# flip_lamp.net
KiCad netlist of a schematic drawn in EAGLE
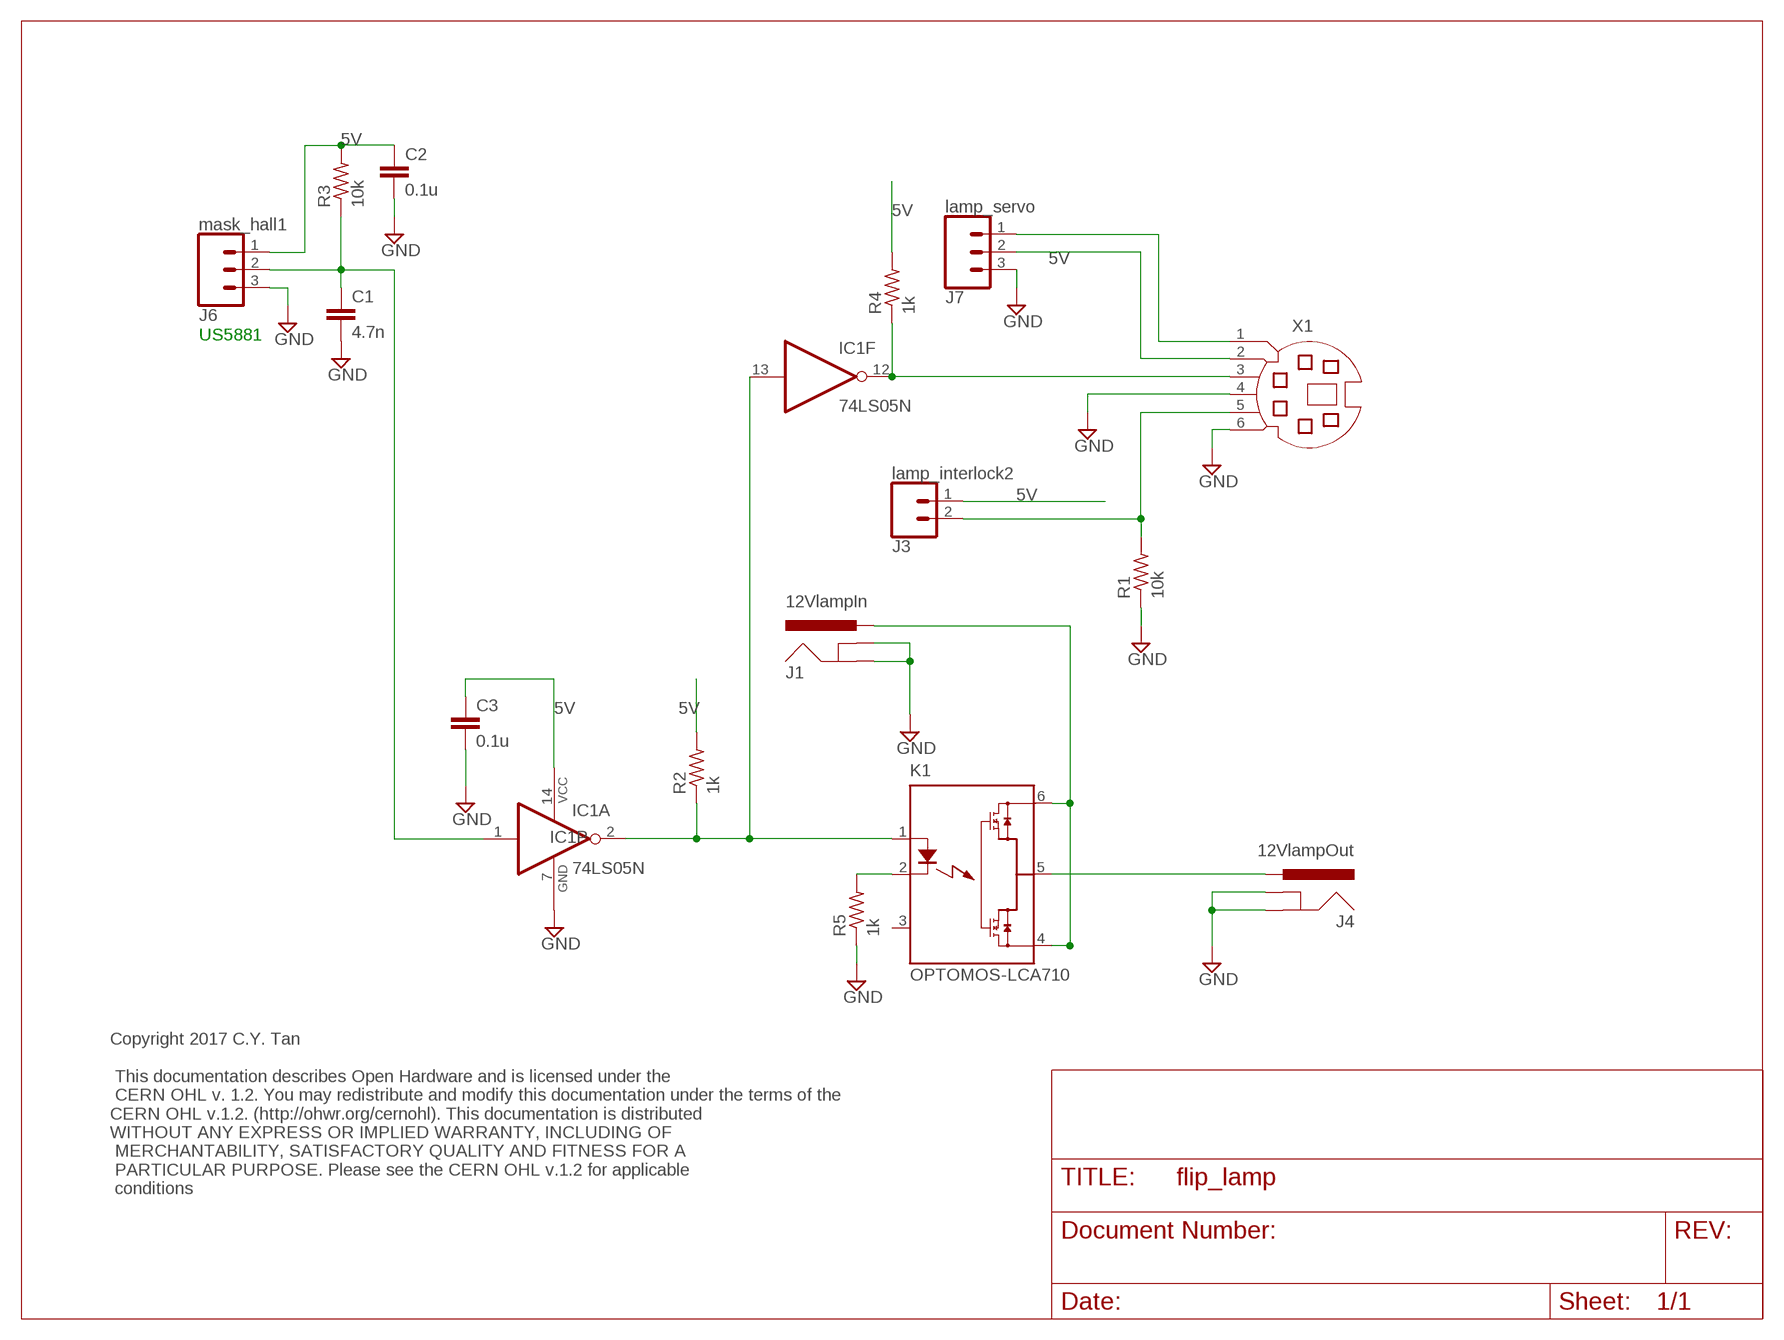
[diagram p0: schematic, sheet 1]

(export (version "E")
  (design (tool "Eeschema 10.0.6"))
  (components
    (comp (ref "C1")
      (value "4.7n")
      (footprint "eagle-import:CAP-PTH-5MM")
      (libsource (lib "eagle-import") (part "CAPPTH1"))
    )
    (comp (ref "C2")
      (value "0.1u")
      (footprint "eagle-import:CAP-PTH-5MM")
      (libsource (lib "eagle-import") (part "CAPPTH1"))
    )
    (comp (ref "C3")
      (value "0.1u")
      (footprint "eagle-import:CAP-PTH-5MM")
      (libsource (lib "eagle-import") (part "CAPPTH1"))
    )
    (comp (ref "IC1")
      (value "74LS05N")
      (footprint "eagle-import:DIL14")
      (libsource (lib "eagle-import") (part "7405NLS"))
    )
    (comp (ref "J1")
      (value "12VlampIn")
      (footprint "eagle-import:POWER_JACK_PTH")
      (libsource (lib "eagle-import") (part "POWER_JACK"))
    )
    (comp (ref "J3")
      (value "lamp_interlock2")
      (footprint "eagle-import:1X02")
      (libsource (lib "eagle-import") (part "CONN_02"))
    )
    (comp (ref "J4")
      (value "12VlampOut")
      (footprint "eagle-import:POWER_JACK_PTH")
      (libsource (lib "eagle-import") (part "POWER_JACK"))
    )
    (comp (ref "J6")
      (value "mask_hall1")
      (footprint "eagle-import:1X03")
      (libsource (lib "eagle-import") (part "CONN_03"))
    )
    (comp (ref "J7")
      (value "lamp_servo")
      (footprint "eagle-import:1X03")
      (libsource (lib "eagle-import") (part "CONN_03"))
    )
    (comp (ref "K1")
      (value "OPTOMOS-LCA710")
      (footprint "eagle-import:DIL6")
      (libsource (lib "eagle-import") (part "OPTOMOS-LCA710"))
    )
    (comp (ref "R1")
      (value "10k")
      (footprint "eagle-import:0207_10")
      (libsource (lib "eagle-import") (part "R-US_0207/10"))
    )
    (comp (ref "R2")
      (value "1k")
      (footprint "eagle-import:0207_10")
      (libsource (lib "eagle-import") (part "R-US_0207/10"))
    )
    (comp (ref "R3")
      (value "10k")
      (footprint "eagle-import:0207_10")
      (libsource (lib "eagle-import") (part "R-US_0207/10"))
    )
    (comp (ref "R4")
      (value "1k")
      (footprint "eagle-import:0207_10")
      (libsource (lib "eagle-import") (part "R-US_0207/10"))
    )
    (comp (ref "R5")
      (value "1k")
      (footprint "eagle-import:0207_10")
      (libsource (lib "eagle-import") (part "R-US_0207/10"))
    )
    (comp (ref "X1")
      (value "MD06SS")
      (footprint "eagle-import:MDIN06SS")
      (libsource (lib "eagle-import") (part "MD06SS"))
    )
  )
  (nets
    (net (code "1") (name "/5V") (class "Default")
      (node (ref "C2") (pin "1") (pinfunction "1_1") (pintype "passive"))
      (node (ref "C3") (pin "1") (pinfunction "1_1") (pintype "passive"))
      (node (ref "IC1") (pin "14") (pinfunction "VCC_14") (pintype "power_in"))
      (node (ref "J3") (pin "1") (pinfunction "1_1") (pintype "passive"))
      (node (ref "J6") (pin "1") (pinfunction "1_1") (pintype "passive"))
      (node (ref "J7") (pin "2") (pinfunction "2_2") (pintype "passive"))
      (node (ref "R2") (pin "2") (pinfunction "2_2") (pintype "passive"))
      (node (ref "R3") (pin "2") (pinfunction "2_2") (pintype "passive"))
      (node (ref "R4") (pin "2") (pinfunction "2_2") (pintype "passive"))
      (node (ref "X1") (pin "2") (pinfunction "2_2") (pintype "passive"))
    )
    (net (code "2") (name "GND") (class "Default")
      (node (ref "C1") (pin "2") (pinfunction "2_2") (pintype "passive"))
      (node (ref "C2") (pin "2") (pinfunction "2_2") (pintype "passive"))
      (node (ref "C3") (pin "2") (pinfunction "2_2") (pintype "passive"))
      (node (ref "IC1") (pin "7") (pinfunction "GND_7") (pintype "power_in"))
      (node (ref "J1") (pin "GND") (pinfunction "GND_GND") (pintype "bidirectional"))
      (node (ref "J1") (pin "GNDBREAK") (pinfunction "GNDBREAK_GNDBREAK") (pintype "bidirectional"))
      (node (ref "J4") (pin "GND") (pinfunction "GND_GND") (pintype "bidirectional"))
      (node (ref "J4") (pin "GNDBREAK") (pinfunction "GNDBREAK_GNDBREAK") (pintype "bidirectional"))
      (node (ref "J6") (pin "3") (pinfunction "3_3") (pintype "passive"))
      (node (ref "J7") (pin "3") (pinfunction "3_3") (pintype "passive"))
      (node (ref "R1") (pin "1") (pinfunction "1_1") (pintype "passive"))
      (node (ref "R5") (pin "1") (pinfunction "1_1") (pintype "passive"))
      (node (ref "X1") (pin "4") (pinfunction "4_4") (pintype "passive"))
      (node (ref "X1") (pin "6") (pinfunction "6_6") (pintype "passive"))
    )
    (net (code "3") (name "Net-(IC1A-I)") (class "Default")
      (node (ref "C1") (pin "1") (pinfunction "1_1") (pintype "passive"))
      (node (ref "IC1") (pin "1") (pinfunction "I_1") (pintype "input"))
      (node (ref "J6") (pin "2") (pinfunction "2_2") (pintype "passive"))
      (node (ref "R3") (pin "1") (pinfunction "1_1") (pintype "passive"))
    )
    (net (code "4") (name "Net-(IC1A-O)") (class "Default")
      (node (ref "IC1") (pin "13") (pinfunction "I_13") (pintype "input"))
      (node (ref "IC1") (pin "2") (pinfunction "O_2") (pintype "open_collector"))
      (node (ref "K1") (pin "1") (pinfunction "A_1") (pintype "passive"))
      (node (ref "R2") (pin "1") (pinfunction "1_1") (pintype "passive"))
    )
    (net (code "5") (name "Net-(IC1F-O)") (class "Default")
      (node (ref "IC1") (pin "12") (pinfunction "O_12") (pintype "open_collector"))
      (node (ref "R4") (pin "1") (pinfunction "1_1") (pintype "passive"))
      (node (ref "X1") (pin "3") (pinfunction "3_3") (pintype "passive"))
    )
    (net (code "6") (name "Net-(J3-Pad2)") (class "Default")
      (node (ref "J3") (pin "2") (pinfunction "2_2") (pintype "passive"))
      (node (ref "R1") (pin "2") (pinfunction "2_2") (pintype "passive"))
      (node (ref "X1") (pin "5") (pinfunction "5_5") (pintype "passive"))
    )
    (net (code "7") (name "Net-(J7-Pad1)") (class "Default")
      (node (ref "J7") (pin "1") (pinfunction "1_1") (pintype "passive"))
      (node (ref "X1") (pin "1") (pinfunction "1_1") (pintype "passive"))
    )
    (net (code "8") (name "Net-(K1-DS1)") (class "Default")
      (node (ref "J1") (pin "PWR") (pinfunction "PWR_PWR") (pintype "bidirectional"))
      (node (ref "K1") (pin "4") (pinfunction "DS3_4") (pintype "passive"))
      (node (ref "K1") (pin "6") (pinfunction "DS1_6") (pintype "passive"))
    )
    (net (code "9") (name "Net-(K1-DS2)") (class "Default")
      (node (ref "J4") (pin "PWR") (pinfunction "PWR_PWR") (pintype "bidirectional"))
      (node (ref "K1") (pin "5") (pinfunction "DS2_5") (pintype "passive"))
    )
    (net (code "10") (name "Net-(K1-K)") (class "Default")
      (node (ref "K1") (pin "2") (pinfunction "K_2") (pintype "passive"))
      (node (ref "R5") (pin "2") (pinfunction "2_2") (pintype "passive"))
    )
    (net (code "11") (name "unconnected-(K1-NC-Pad3)") (class "Default")
      (node (ref "K1") (pin "3") (pinfunction "NC_3") (pintype "no_connect"))
    )
  )
)
